# Part16_I2C_MPU9250.net
KiCad netlist of a schematic drawn in Altium Designer
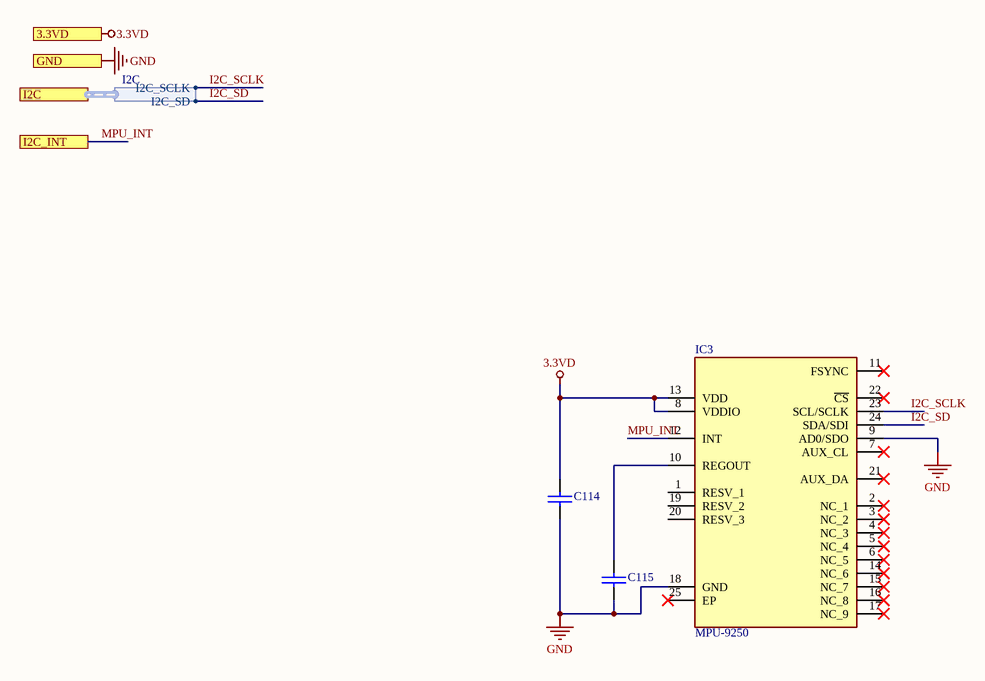
[diagram p0: Part16_I2C_MPU9250.SchDoc]

(export (version "E")
  (design (tool "Eeschema 10.0.6"))
  (components
    (comp (ref "C114")
      (value "100nF")
      (footprint "0402C")
      (description "无极性电容")
      (libsource (lib "电容") (part "CAP"))
    )
    (comp (ref "C115")
      (value "100nF")
      (footprint "0402C")
      (description "无极性电容")
      (libsource (lib "电容") (part "CAP"))
    )
    (comp (ref "IC3")
      (value "MPU-9250")
      (footprint "SamacSys:QFN40P300X300X105-25N-D")
      (description "Integrated Circuit")
      (fields (field (name "MOUSER PART NUMBER") "410-MPU-9250"))
      (libsource (lib "SamacSys") (part "MPU-9250"))
    )
  )
  (nets
    (net (code "2") (name "/I2C_SCLK") (class "Default")
      (node (ref "IC3") (pin "23") (pinfunction "SCL/SCLK_23") (pintype "passive"))
    )
    (net (code "3") (name "/I2C_SD") (class "Default")
      (node (ref "IC3") (pin "24") (pinfunction "SDA/SDI_24") (pintype "passive"))
    )
    (net (code "4") (name "/MPU_INT") (class "Default")
      (node (ref "IC3") (pin "12") (pinfunction "INT_12") (pintype "passive"))
    )
    (net (code "6") (name "3.3VD") (class "Default")
      (node (ref "C114") (pin "1") (pinfunction "1_1") (pintype "passive"))
      (node (ref "IC3") (pin "13") (pinfunction "VDD_13") (pintype "passive"))
      (node (ref "IC3") (pin "8") (pinfunction "VDDIO_8") (pintype "passive"))
    )
    (net (code "7") (name "GND") (class "Default")
      (node (ref "C114") (pin "2") (pinfunction "2_2") (pintype "passive"))
      (node (ref "C115") (pin "2") (pinfunction "2_2") (pintype "passive"))
      (node (ref "IC3") (pin "18") (pinfunction "GND_18") (pintype "passive"))
      (node (ref "IC3") (pin "9") (pinfunction "AD0/SDO_9") (pintype "passive"))
    )
    (net (code "8") (name "Net-(IC3-REGOUT)") (class "Default")
      (node (ref "C115") (pin "1") (pinfunction "1_1") (pintype "passive"))
      (node (ref "IC3") (pin "10") (pinfunction "REGOUT_10") (pintype "passive"))
    )
    (net (code "9") (name "unconnected-(IC3-AUX_CL-Pad7)") (class "Default")
      (node (ref "IC3") (pin "7") (pinfunction "AUX_CL_7") (pintype "passive+no_connect"))
    )
    (net (code "10") (name "unconnected-(IC3-AUX_DA-Pad21)") (class "Default")
      (node (ref "IC3") (pin "21") (pinfunction "AUX_DA_21") (pintype "passive+no_connect"))
    )
    (net (code "11") (name "unconnected-(IC3-EP-Pad25)") (class "Default")
      (node (ref "IC3") (pin "25") (pinfunction "EP_25") (pintype "passive+no_connect"))
    )
    (net (code "12") (name "unconnected-(IC3-FSYNC-Pad11)") (class "Default")
      (node (ref "IC3") (pin "11") (pinfunction "FSYNC_11") (pintype "passive+no_connect"))
    )
    (net (code "13") (name "unconnected-(IC3-NC_1-Pad2)") (class "Default")
      (node (ref "IC3") (pin "2") (pinfunction "NC_1_2") (pintype "passive+no_connect"))
    )
    (net (code "14") (name "unconnected-(IC3-NC_2-Pad3)") (class "Default")
      (node (ref "IC3") (pin "3") (pinfunction "NC_2_3") (pintype "passive+no_connect"))
    )
    (net (code "15") (name "unconnected-(IC3-NC_3-Pad4)") (class "Default")
      (node (ref "IC3") (pin "4") (pinfunction "NC_3_4") (pintype "passive+no_connect"))
    )
    (net (code "16") (name "unconnected-(IC3-NC_4-Pad5)") (class "Default")
      (node (ref "IC3") (pin "5") (pinfunction "NC_4_5") (pintype "passive+no_connect"))
    )
    (net (code "17") (name "unconnected-(IC3-NC_5-Pad6)") (class "Default")
      (node (ref "IC3") (pin "6") (pinfunction "NC_5_6") (pintype "passive+no_connect"))
    )
    (net (code "18") (name "unconnected-(IC3-NC_6-Pad14)") (class "Default")
      (node (ref "IC3") (pin "14") (pinfunction "NC_6_14") (pintype "passive+no_connect"))
    )
    (net (code "19") (name "unconnected-(IC3-NC_7-Pad15)") (class "Default")
      (node (ref "IC3") (pin "15") (pinfunction "NC_7_15") (pintype "passive+no_connect"))
    )
    (net (code "20") (name "unconnected-(IC3-NC_8-Pad16)") (class "Default")
      (node (ref "IC3") (pin "16") (pinfunction "NC_8_16") (pintype "passive+no_connect"))
    )
    (net (code "21") (name "unconnected-(IC3-NC_9-Pad17)") (class "Default")
      (node (ref "IC3") (pin "17") (pinfunction "NC_9_17") (pintype "passive+no_connect"))
    )
    (net (code "22") (name "unconnected-(IC3-RESV_1-Pad1)") (class "Default")
      (node (ref "IC3") (pin "1") (pinfunction "RESV_1_1") (pintype "passive"))
    )
    (net (code "23") (name "unconnected-(IC3-RESV_2-Pad19)") (class "Default")
      (node (ref "IC3") (pin "19") (pinfunction "RESV_2_19") (pintype "passive"))
    )
    (net (code "24") (name "unconnected-(IC3-RESV_3-Pad20)") (class "Default")
      (node (ref "IC3") (pin "20") (pinfunction "RESV_3_20") (pintype "passive"))
    )
    (net (code "25") (name "unconnected-(IC3-~{CS}-Pad22)") (class "Default")
      (node (ref "IC3") (pin "22") (pinfunction "~{CS}_22") (pintype "passive+no_connect"))
    )
  )
)
